# test.net
KiCad netlist of a schematic drawn in EAGLE
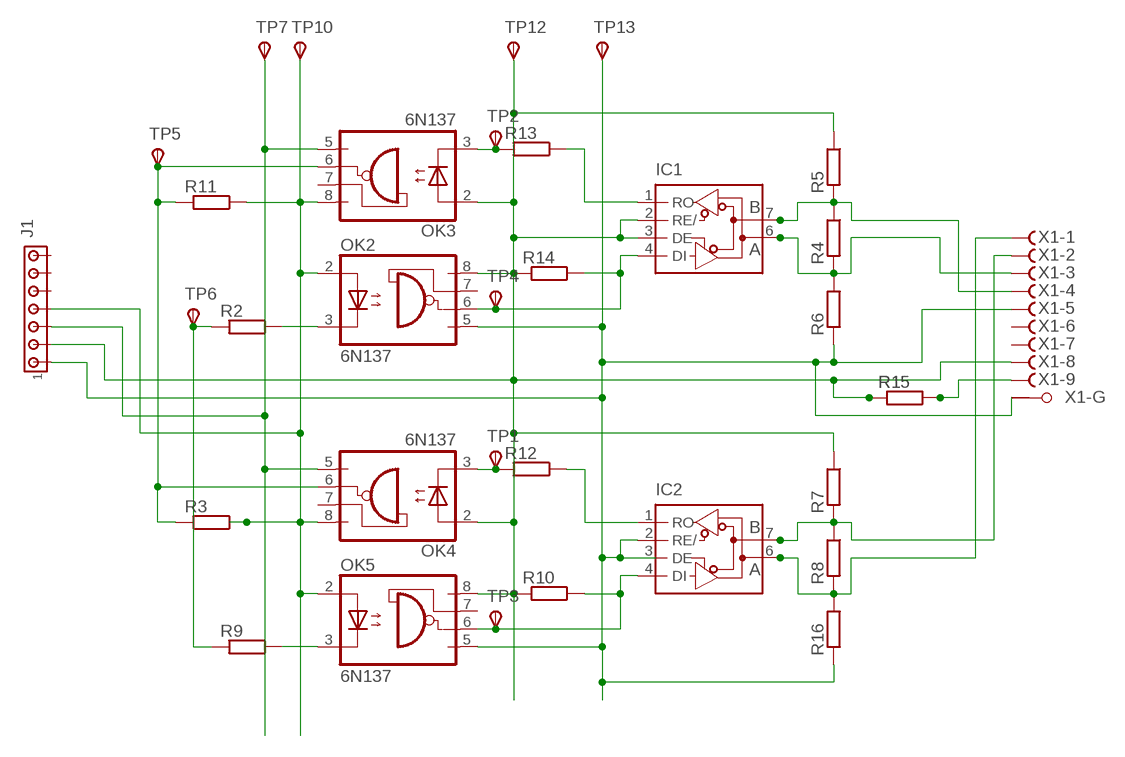
[diagram p0: schematic, sheet 1]

(export (version "E")
  (design (tool "Eeschema 10.0.6"))
  (components
    (comp (ref "IC1")
      (value "MAX481CSA")
      (footprint "eagle-import:SO08")
      (libsource (lib "eagle-import") (part "MAX481CSA"))
    )
    (comp (ref "IC2")
      (value "MAX481CSA")
      (footprint "eagle-import:SO08")
      (libsource (lib "eagle-import") (part "MAX481CSA"))
    )
    (comp (ref "J1")
      (value "MTA07-100")
      (footprint "eagle-import:10X07MTA")
      (libsource (lib "eagle-import") (part "MTA07-100"))
    )
    (comp (ref "OK2")
      (value "6N137")
      (footprint "eagle-import:DIL08")
      (libsource (lib "eagle-import") (part "6N137"))
    )
    (comp (ref "OK3")
      (value "6N137")
      (footprint "eagle-import:DIL08")
      (libsource (lib "eagle-import") (part "6N137"))
    )
    (comp (ref "OK4")
      (value "6N137")
      (footprint "eagle-import:DIL08")
      (libsource (lib "eagle-import") (part "6N137"))
    )
    (comp (ref "OK5")
      (value "6N137")
      (footprint "eagle-import:DIL08")
      (libsource (lib "eagle-import") (part "6N137"))
    )
    (comp (ref "R1")
      (value "SMK")
      (footprint "eagle-import:SMK")
      (libsource (lib "eagle-import") (part "SMK"))
    )
    (comp (ref "R2")
      (value "SMK")
      (footprint "eagle-import:SMK")
      (libsource (lib "eagle-import") (part "SMK"))
    )
    (comp (ref "R3")
      (value "SMK")
      (footprint "eagle-import:SMK")
      (libsource (lib "eagle-import") (part "SMK"))
    )
    (comp (ref "R4")
      (value "SMK")
      (footprint "eagle-import:SMK")
      (libsource (lib "eagle-import") (part "SMK"))
    )
    (comp (ref "R5")
      (value "SMK")
      (footprint "eagle-import:SMK")
      (libsource (lib "eagle-import") (part "SMK"))
    )
    (comp (ref "R6")
      (value "SMK")
      (footprint "eagle-import:SMK")
      (libsource (lib "eagle-import") (part "SMK"))
    )
    (comp (ref "R7")
      (value "SMK")
      (footprint "eagle-import:SMK")
      (libsource (lib "eagle-import") (part "SMK"))
    )
    (comp (ref "R8")
      (value "SMK")
      (footprint "eagle-import:SMK")
      (libsource (lib "eagle-import") (part "SMK"))
    )
    (comp (ref "R9")
      (value "SMK")
      (footprint "eagle-import:SMK")
      (libsource (lib "eagle-import") (part "SMK"))
    )
    (comp (ref "R10")
      (value "SMK")
      (footprint "eagle-import:SMK")
      (libsource (lib "eagle-import") (part "SMK"))
    )
    (comp (ref "R11")
      (value "SMK")
      (footprint "eagle-import:SMK")
      (libsource (lib "eagle-import") (part "SMK"))
    )
    (comp (ref "R12")
      (value "SMK")
      (footprint "eagle-import:SMK")
      (libsource (lib "eagle-import") (part "SMK"))
    )
    (comp (ref "R13")
      (value "SMK")
      (footprint "eagle-import:SMK")
      (libsource (lib "eagle-import") (part "SMK"))
    )
    (comp (ref "R14")
      (value "SMK")
      (footprint "eagle-import:SMK")
      (libsource (lib "eagle-import") (part "SMK"))
    )
    (comp (ref "R15")
      (value "SMK")
      (footprint "eagle-import:SMK")
      (libsource (lib "eagle-import") (part "SMK"))
    )
    (comp (ref "R16")
      (value "SMK")
      (footprint "eagle-import:SMK")
      (libsource (lib "eagle-import") (part "SMK"))
    )
    (comp (ref "TP1")
      (value "TPSB2,54")
      (footprint "eagle-import:B2,54")
      (libsource (lib "eagle-import") (part "TPSB2,54"))
    )
    (comp (ref "TP2")
      (value "TPSB2,54")
      (footprint "eagle-import:B2,54")
      (libsource (lib "eagle-import") (part "TPSB2,54"))
    )
    (comp (ref "TP3")
      (value "TPSB2,54")
      (footprint "eagle-import:B2,54")
      (libsource (lib "eagle-import") (part "TPSB2,54"))
    )
    (comp (ref "TP4")
      (value "TPSB2,54")
      (footprint "eagle-import:B2,54")
      (libsource (lib "eagle-import") (part "TPSB2,54"))
    )
    (comp (ref "TP5")
      (value "TPSB2,54")
      (footprint "eagle-import:B2,54")
      (libsource (lib "eagle-import") (part "TPSB2,54"))
    )
    (comp (ref "TP6")
      (value "TPSB2,54")
      (footprint "eagle-import:B2,54")
      (libsource (lib "eagle-import") (part "TPSB2,54"))
    )
    (comp (ref "TP7")
      (value "TPSB2,54")
      (footprint "eagle-import:B2,54")
      (libsource (lib "eagle-import") (part "TPSB2,54"))
    )
    (comp (ref "TP10")
      (value "TPSB2,54")
      (footprint "eagle-import:B2,54")
      (libsource (lib "eagle-import") (part "TPSB2,54"))
    )
    (comp (ref "TP12")
      (value "TPSB2,54")
      (footprint "eagle-import:B2,54")
      (libsource (lib "eagle-import") (part "TPSB2,54"))
    )
    (comp (ref "TP13")
      (value "TPSB2,54")
      (footprint "eagle-import:B2,54")
      (libsource (lib "eagle-import") (part "TPSB2,54"))
    )
    (comp (ref "X1")
      (value "F09HPS")
      (footprint "eagle-import:F09HP")
      (libsource (lib "eagle-import") (part "F09HPS"))
    )
  )
  (nets
    (net (code "1") (name "Net-(IC1B-A)") (class "Default")
      (node (ref "IC1") (pin "6") (pinfunction "A_6") (pintype "passive"))
      (node (ref "R4") (pin "2") (pinfunction "2_2") (pintype "passive"))
      (node (ref "R6") (pin "1") (pinfunction "1_1") (pintype "passive"))
      (node (ref "X1") (pin "3") (pinfunction "F_3") (pintype "passive"))
    )
    (net (code "2") (name "Net-(IC1B-B)") (class "Default")
      (node (ref "IC1") (pin "7") (pinfunction "B_7") (pintype "passive"))
      (node (ref "R4") (pin "1") (pinfunction "1_1") (pintype "passive"))
      (node (ref "R5") (pin "2") (pinfunction "2_2") (pintype "passive"))
      (node (ref "X1") (pin "4") (pinfunction "F_4") (pintype "passive"))
    )
    (net (code "3") (name "Net-(IC1B-DE)") (class "Default")
      (node (ref "IC1") (pin "2") (pinfunction "RE/_2") (pintype "input"))
      (node (ref "IC1") (pin "3") (pinfunction "DE_3") (pintype "input"))
      (node (ref "J1") (pin "2") (pinfunction "2_2") (pintype "passive"))
      (node (ref "OK2") (pin "8") (pinfunction "VCC_8") (pintype "passive"))
      (node (ref "OK3") (pin "2") (pinfunction "A_2") (pintype "passive"))
      (node (ref "OK4") (pin "2") (pinfunction "A_2") (pintype "passive"))
      (node (ref "OK5") (pin "8") (pinfunction "VCC_8") (pintype "passive"))
      (node (ref "R1") (pin "2") (pinfunction "2_2") (pintype "passive"))
      (node (ref "R10") (pin "2") (pinfunction "2_2") (pintype "passive"))
      (node (ref "R14") (pin "2") (pinfunction "2_2") (pintype "passive"))
      (node (ref "R15") (pin "2") (pinfunction "2_2") (pintype "passive"))
      (node (ref "R5") (pin "1") (pinfunction "1_1") (pintype "passive"))
      (node (ref "R7") (pin "1") (pinfunction "1_1") (pintype "passive"))
      (node (ref "TP12") (pin "TP") (pinfunction "PP_TP") (pintype "input"))
      (node (ref "X1") (pin "8") (pinfunction "F_8") (pintype "passive"))
    )
    (net (code "4") (name "Net-(IC1B-DI)") (class "Default")
      (node (ref "IC1") (pin "4") (pinfunction "DI_4") (pintype "input"))
      (node (ref "OK2") (pin "6") (pinfunction "VO_6") (pintype "passive"))
      (node (ref "R14") (pin "1") (pinfunction "1_1") (pintype "passive"))
      (node (ref "TP4") (pin "TP") (pinfunction "PP_TP") (pintype "input"))
    )
    (net (code "5") (name "Net-(IC1B-RO)") (class "Default")
      (node (ref "IC1") (pin "1") (pinfunction "RO_1") (pintype "output"))
      (node (ref "R13") (pin "1") (pinfunction "1_1") (pintype "passive"))
    )
    (net (code "6") (name "Net-(IC2B-A)") (class "Default")
      (node (ref "IC2") (pin "6") (pinfunction "A_6") (pintype "passive"))
      (node (ref "R16") (pin "1") (pinfunction "1_1") (pintype "passive"))
      (node (ref "R8") (pin "2") (pinfunction "2_2") (pintype "passive"))
      (node (ref "X1") (pin "1") (pinfunction "F_1") (pintype "passive"))
    )
    (net (code "7") (name "Net-(IC2B-B)") (class "Default")
      (node (ref "IC2") (pin "7") (pinfunction "B_7") (pintype "passive"))
      (node (ref "R7") (pin "2") (pinfunction "2_2") (pintype "passive"))
      (node (ref "R8") (pin "1") (pinfunction "1_1") (pintype "passive"))
      (node (ref "X1") (pin "2") (pinfunction "F_2") (pintype "passive"))
    )
    (net (code "8") (name "Net-(IC2B-DI)") (class "Default")
      (node (ref "IC2") (pin "4") (pinfunction "DI_4") (pintype "input"))
      (node (ref "OK5") (pin "6") (pinfunction "VO_6") (pintype "passive"))
      (node (ref "R10") (pin "1") (pinfunction "1_1") (pintype "passive"))
      (node (ref "TP3") (pin "TP") (pinfunction "PP_TP") (pintype "input"))
    )
    (net (code "9") (name "Net-(IC2B-RE{slash})") (class "Default")
      (node (ref "IC2") (pin "2") (pinfunction "RE/_2") (pintype "input"))
      (node (ref "J1") (pin "1") (pinfunction "1_1") (pintype "passive"))
      (node (ref "OK2") (pin "5") (pinfunction "GND_5") (pintype "passive"))
      (node (ref "OK5") (pin "5") (pinfunction "GND_5") (pintype "passive"))
      (node (ref "R16") (pin "2") (pinfunction "2_2") (pintype "passive"))
      (node (ref "R6") (pin "2") (pinfunction "2_2") (pintype "passive"))
      (node (ref "TP13") (pin "TP") (pinfunction "PP_TP") (pintype "input"))
      (node (ref "X1") (pin "5") (pinfunction "F_5") (pintype "passive"))
      (node (ref "X1") (pin "G1") (pinfunction "G1_G1") (pintype "passive"))
    )
    (net (code "10") (name "Net-(IC2B-RO)") (class "Default")
      (node (ref "IC2") (pin "1") (pinfunction "RO_1") (pintype "output"))
      (node (ref "R12") (pin "1") (pinfunction "1_1") (pintype "passive"))
    )
    (net (code "11") (name "Net-(OK2-A)") (class "Default")
      (node (ref "J1") (pin "4") (pinfunction "4_4") (pintype "passive"))
      (node (ref "OK2") (pin "2") (pinfunction "A_2") (pintype "passive"))
      (node (ref "OK3") (pin "8") (pinfunction "VCC_8") (pintype "passive"))
      (node (ref "OK4") (pin "8") (pinfunction "VCC_8") (pintype "passive"))
      (node (ref "OK5") (pin "2") (pinfunction "A_2") (pintype "passive"))
      (node (ref "R11") (pin "1") (pinfunction "1_1") (pintype "passive"))
      (node (ref "R3") (pin "1") (pinfunction "1_1") (pintype "passive"))
      (node (ref "TP10") (pin "TP") (pinfunction "PP_TP") (pintype "input"))
    )
    (net (code "12") (name "Net-(OK2-C)") (class "Default")
      (node (ref "OK2") (pin "3") (pinfunction "C_3") (pintype "passive"))
      (node (ref "R2") (pin "1") (pinfunction "1_1") (pintype "passive"))
    )
    (net (code "13") (name "Net-(OK3-C)") (class "Default")
      (node (ref "OK3") (pin "3") (pinfunction "C_3") (pintype "passive"))
      (node (ref "R13") (pin "2") (pinfunction "2_2") (pintype "passive"))
      (node (ref "TP2") (pin "TP") (pinfunction "PP_TP") (pintype "input"))
    )
    (net (code "14") (name "Net-(OK3-GND)") (class "Default")
      (node (ref "J1") (pin "3") (pinfunction "3_3") (pintype "passive"))
      (node (ref "OK3") (pin "5") (pinfunction "GND_5") (pintype "passive"))
      (node (ref "OK4") (pin "5") (pinfunction "GND_5") (pintype "passive"))
      (node (ref "TP7") (pin "TP") (pinfunction "PP_TP") (pintype "input"))
    )
    (net (code "15") (name "Net-(OK3-VO)") (class "Default")
      (node (ref "OK3") (pin "6") (pinfunction "VO_6") (pintype "passive"))
      (node (ref "OK4") (pin "6") (pinfunction "VO_6") (pintype "passive"))
      (node (ref "R11") (pin "2") (pinfunction "2_2") (pintype "passive"))
      (node (ref "R3") (pin "2") (pinfunction "2_2") (pintype "passive"))
      (node (ref "TP5") (pin "TP") (pinfunction "PP_TP") (pintype "input"))
    )
    (net (code "16") (name "Net-(OK4-C)") (class "Default")
      (node (ref "OK4") (pin "3") (pinfunction "C_3") (pintype "passive"))
      (node (ref "R12") (pin "2") (pinfunction "2_2") (pintype "passive"))
      (node (ref "TP1") (pin "TP") (pinfunction "PP_TP") (pintype "input"))
    )
    (net (code "17") (name "Net-(OK5-C)") (class "Default")
      (node (ref "OK5") (pin "3") (pinfunction "C_3") (pintype "passive"))
      (node (ref "R9") (pin "1") (pinfunction "1_1") (pintype "passive"))
    )
    (net (code "18") (name "Net-(TP6-PP)") (class "Default")
      (node (ref "R2") (pin "2") (pinfunction "2_2") (pintype "passive"))
      (node (ref "R9") (pin "2") (pinfunction "2_2") (pintype "passive"))
      (node (ref "TP6") (pin "TP") (pinfunction "PP_TP") (pintype "input"))
    )
    (net (code "19") (name "Net-(X1I-F)") (class "Default")
      (node (ref "R1") (pin "1") (pinfunction "1_1") (pintype "passive"))
      (node (ref "R15") (pin "1") (pinfunction "1_1") (pintype "passive"))
      (node (ref "X1") (pin "9") (pinfunction "F_9") (pintype "passive"))
    )
    (net (code "20") (name "unconnected-(IC2B-DE-Pad3)") (class "Default")
      (node (ref "IC2") (pin "3") (pinfunction "DE_3") (pintype "input"))
    )
    (net (code "21") (name "unconnected-(J1-Pad5)") (class "Default")
      (node (ref "J1") (pin "5") (pinfunction "5_5") (pintype "passive"))
    )
    (net (code "22") (name "unconnected-(J1-Pad6)") (class "Default")
      (node (ref "J1") (pin "6") (pinfunction "6_6") (pintype "passive"))
    )
    (net (code "23") (name "unconnected-(J1-Pad7)") (class "Default")
      (node (ref "J1") (pin "7") (pinfunction "7_7") (pintype "passive"))
    )
    (net (code "24") (name "unconnected-(OK2-VE-Pad7)") (class "Default")
      (node (ref "OK2") (pin "7") (pinfunction "VE_7") (pintype "passive"))
    )
    (net (code "25") (name "unconnected-(OK3-VE-Pad7)") (class "Default")
      (node (ref "OK3") (pin "7") (pinfunction "VE_7") (pintype "passive"))
    )
    (net (code "26") (name "unconnected-(OK4-VE-Pad7)") (class "Default")
      (node (ref "OK4") (pin "7") (pinfunction "VE_7") (pintype "passive"))
    )
    (net (code "27") (name "unconnected-(OK5-VE-Pad7)") (class "Default")
      (node (ref "OK5") (pin "7") (pinfunction "VE_7") (pintype "passive"))
    )
    (net (code "28") (name "unconnected-(X1-PadG2)") (class "Default")
      (node (ref "X1") (pin "G2") (pinfunction "G2_G2") (pintype "passive"))
    )
    (net (code "29") (name "unconnected-(X1F-F-Pad6)") (class "Default")
      (node (ref "X1") (pin "6") (pinfunction "F_6") (pintype "passive"))
    )
    (net (code "30") (name "unconnected-(X1G-F-Pad7)") (class "Default")
      (node (ref "X1") (pin "7") (pinfunction "F_7") (pintype "passive"))
    )
  )
)
